# ETH_1G_MAGNET_HX5084.net
KiCad netlist of a schematic drawn in Altium Designer
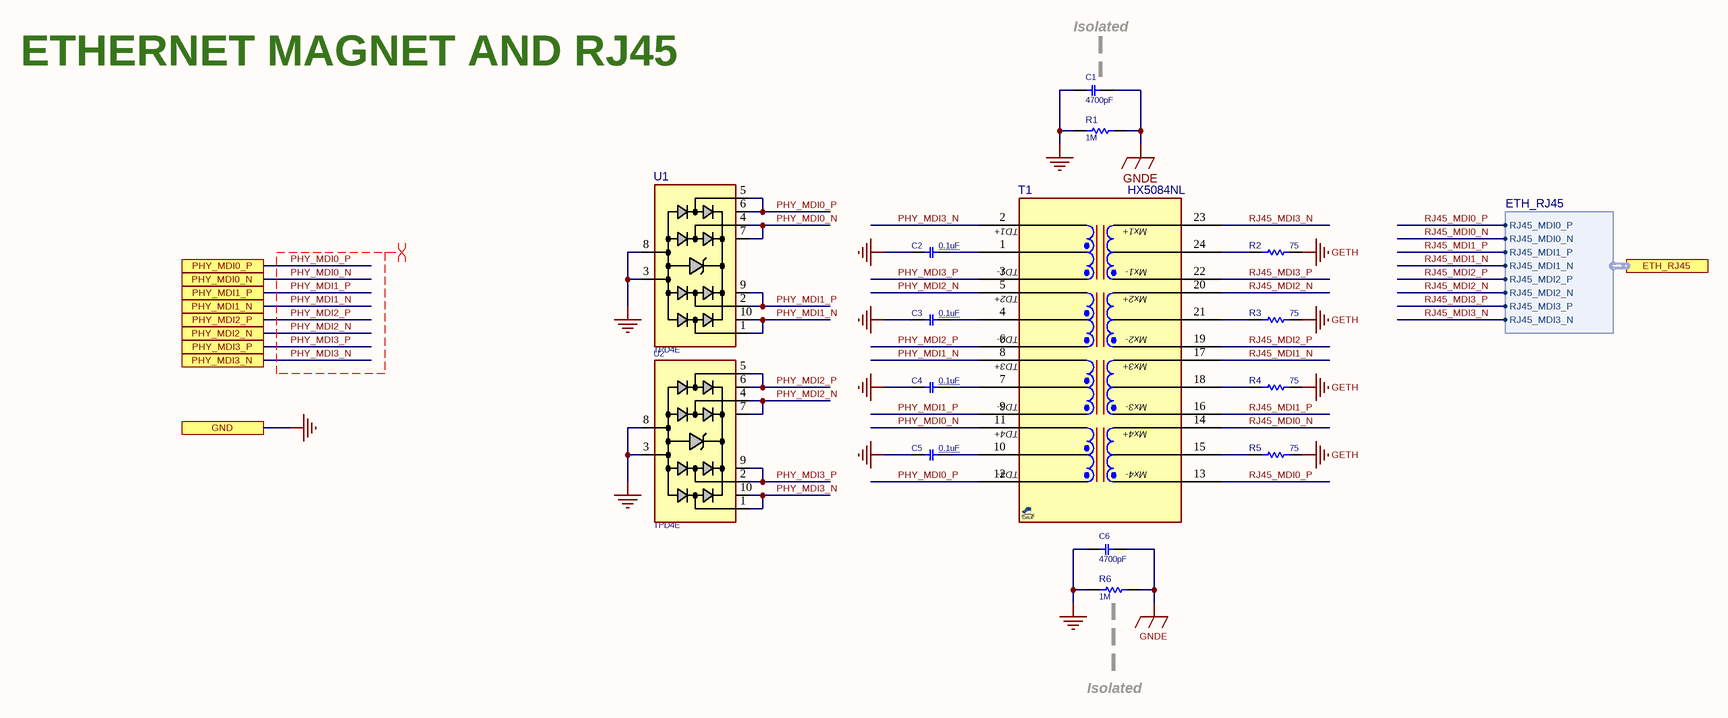
[diagram p0: ETH_1G_MAGNET_HX5084.SchDoc]

(export (version "E")
  (design (tool "Eeschema 10.0.6"))
  (components
    (comp (ref "C1")
      (value "4700pF")
      (footprint "C1206")
      (description "CAP, MLCC")
      (fields (field (name "MANF_P#") "NV1206B472K202CEGN") (field (name "MANF") "KEMET"))
      (libsource (lib "mlcc_smd_passive") (part "CAP_SMD_MLCC_68n1kv"))
    )
    (comp (ref "C2")
      (value "0.1uF")
      (footprint "C0402")
      (description "CAP, MLCC")
      (fields (field (name "MANF_P#") "MANF_PART#"))
      (libsource (lib "passive_smd") (part "CAP_SMD_MLCC_0402"))
    )
    (comp (ref "C3")
      (value "0.1uF")
      (footprint "C0402")
      (description "CAP, MLCC")
      (fields (field (name "MANF_P#") "MANF_PART#"))
      (libsource (lib "passive_smd") (part "CAP_SMD_MLCC_0402"))
    )
    (comp (ref "C4")
      (value "0.1uF")
      (footprint "C0402")
      (description "CAP, MLCC")
      (fields (field (name "MANF_P#") "MANF_PART#"))
      (libsource (lib "passive_smd") (part "CAP_SMD_MLCC_0402"))
    )
    (comp (ref "C5")
      (value "0.1uF")
      (footprint "C0402")
      (description "CAP, MLCC")
      (fields (field (name "MANF_P#") "MANF_PART#"))
      (libsource (lib "passive_smd") (part "CAP_SMD_MLCC_0402"))
    )
    (comp (ref "C6")
      (value "4700pF")
      (footprint "C1206")
      (description "CAP, MLCC")
      (fields (field (name "MANF_P#") "NV1206B472K202CEGN") (field (name "MANF") "KEMET"))
      (libsource (lib "mlcc_smd_passive") (part "CAP_SMD_MLCC_68n1kv"))
    )
    (comp (ref "R1")
      (value "1M")
      (footprint "R2512")
      (description "RESISTOR, SMD")
      (fields (field (name "MANF_P#") "FRC2512J105 TS"))
      (libsource (lib "chila_passive") (part "RES_SMD"))
    )
    (comp (ref "R2")
      (value "75")
      (footprint "R0402")
      (description "RESISTOR, SMD")
      (libsource (lib "passive_res_smd") (part "RES_SMD"))
    )
    (comp (ref "R3")
      (value "75")
      (footprint "R0402")
      (description "RESISTOR, SMD")
      (libsource (lib "passive_res_smd") (part "RES_SMD"))
    )
    (comp (ref "R4")
      (value "75")
      (footprint "R0402")
      (description "RESISTOR, SMD")
      (libsource (lib "passive_res_smd") (part "RES_SMD"))
    )
    (comp (ref "R5")
      (value "75")
      (footprint "R0402")
      (description "RESISTOR, SMD")
      (libsource (lib "passive_res_smd") (part "RES_SMD"))
    )
    (comp (ref "R6")
      (value "1M")
      (footprint "R2512")
      (description "RESISTOR, SMD")
      (fields (field (name "MANF_P#") "FRC2512J105 TS"))
      (libsource (lib "chila_passive") (part "RES_SMD"))
    )
    (comp (ref "T1")
      (value "HX5084NL")
      (footprint "SOG100_24")
      (description "Transformer, LAN 10/100/1000 Base-T, 1CT:1CT, 350uH")
      (fields (field (name "MANF") "Pulse"))
      (libsource (lib "transformer_ethernet") (part "HX5084NL_SO24"))
    )
    (comp (ref "U1")
      (value "TPD4E")
      (footprint "SON50_10_2510")
      (description "TVS, ESD PROTECT, 4CH,")
      (fields (field (name "MANF_P#") "TPD4E05U06DQA") (field (name "MANF") "Texas Instruments"))
      (libsource (lib "protect_tvs_esd_fuse") (part "TVS_X4_TPD4E05U06"))
    )
    (comp (ref "U2")
      (value "TPD4E")
      (footprint "SON50_10_2510")
      (description "TVS, ESD PROTECT, 4CH,")
      (fields (field (name "MANF_P#") "TPD4E05U06DQA") (field (name "MANF") "Texas Instruments"))
      (libsource (lib "protect_tvs_esd_fuse") (part "TVS_X4_TPD4E05U06"))
    )
  )
  (nets
    (net (code "2") (name "/PHY_MDI0_N") (class "Default")
      (node (ref "T1") (pin "11") (pinfunction "TD4+_11") (pintype "passive"))
      (node (ref "U1") (pin "4") (pinfunction "4_4") (pintype "passive"))
      (node (ref "U1") (pin "7") (pinfunction "7_7") (pintype "passive"))
    )
    (net (code "3") (name "/PHY_MDI0_P") (class "Default")
      (node (ref "T1") (pin "12") (pinfunction "TD4-_12") (pintype "passive"))
      (node (ref "U1") (pin "5") (pinfunction "5_5") (pintype "passive"))
      (node (ref "U1") (pin "6") (pinfunction "6_6") (pintype "passive"))
    )
    (net (code "4") (name "/PHY_MDI1_N") (class "Default")
      (node (ref "T1") (pin "8") (pinfunction "TD3+_8") (pintype "passive"))
      (node (ref "U1") (pin "1") (pinfunction "1_1") (pintype "passive"))
      (node (ref "U1") (pin "10") (pinfunction "10_10") (pintype "passive"))
    )
    (net (code "5") (name "/PHY_MDI1_P") (class "Default")
      (node (ref "T1") (pin "9") (pinfunction "TD3-_9") (pintype "passive"))
      (node (ref "U1") (pin "2") (pinfunction "2_2") (pintype "passive"))
      (node (ref "U1") (pin "9") (pinfunction "9_9") (pintype "passive"))
    )
    (net (code "6") (name "/PHY_MDI2_N") (class "Default")
      (node (ref "T1") (pin "5") (pinfunction "TD2+_5") (pintype "passive"))
      (node (ref "U2") (pin "4") (pinfunction "4_4") (pintype "passive"))
      (node (ref "U2") (pin "7") (pinfunction "7_7") (pintype "passive"))
    )
    (net (code "7") (name "/PHY_MDI2_P") (class "Default")
      (node (ref "T1") (pin "6") (pinfunction "TD2-_6") (pintype "passive"))
      (node (ref "U2") (pin "5") (pinfunction "5_5") (pintype "passive"))
      (node (ref "U2") (pin "6") (pinfunction "6_6") (pintype "passive"))
    )
    (net (code "8") (name "/PHY_MDI3_N") (class "Default")
      (node (ref "T1") (pin "2") (pinfunction "TD1+_2") (pintype "passive"))
      (node (ref "U2") (pin "1") (pinfunction "1_1") (pintype "passive"))
      (node (ref "U2") (pin "10") (pinfunction "10_10") (pintype "passive"))
    )
    (net (code "9") (name "/PHY_MDI3_P") (class "Default")
      (node (ref "T1") (pin "3") (pinfunction "TD1-_3") (pintype "passive"))
      (node (ref "U2") (pin "2") (pinfunction "2_2") (pintype "passive"))
      (node (ref "U2") (pin "9") (pinfunction "9_9") (pintype "passive"))
    )
    (net (code "10") (name "/RJ45_MDI0_N") (class "Default")
      (node (ref "T1") (pin "14") (pinfunction "MX4+_14") (pintype "passive"))
    )
    (net (code "11") (name "/RJ45_MDI0_P") (class "Default")
      (node (ref "T1") (pin "13") (pinfunction "MX4-_13") (pintype "passive"))
    )
    (net (code "12") (name "/RJ45_MDI1_N") (class "Default")
      (node (ref "T1") (pin "17") (pinfunction "MX3+_17") (pintype "passive"))
    )
    (net (code "13") (name "/RJ45_MDI1_P") (class "Default")
      (node (ref "T1") (pin "16") (pinfunction "MX3-_16") (pintype "passive"))
    )
    (net (code "14") (name "/RJ45_MDI2_N") (class "Default")
      (node (ref "T1") (pin "20") (pinfunction "MX2+_20") (pintype "passive"))
    )
    (net (code "15") (name "/RJ45_MDI2_P") (class "Default")
      (node (ref "T1") (pin "19") (pinfunction "MX2-_19") (pintype "passive"))
    )
    (net (code "16") (name "/RJ45_MDI3_N") (class "Default")
      (node (ref "T1") (pin "23") (pinfunction "MX1+_23") (pintype "passive"))
    )
    (net (code "17") (name "/RJ45_MDI3_P") (class "Default")
      (node (ref "T1") (pin "22") (pinfunction "MX1-_22") (pintype "passive"))
    )
    (net (code "19") (name "GETH") (class "Default")
      (node (ref "R2") (pin "1") (pinfunction "1_1") (pintype "passive"))
      (node (ref "R3") (pin "1") (pinfunction "1_1") (pintype "passive"))
      (node (ref "R4") (pin "1") (pinfunction "1_1") (pintype "passive"))
      (node (ref "R5") (pin "1") (pinfunction "1_1") (pintype "passive"))
    )
    (net (code "20") (name "GND") (class "Default")
      (node (ref "C1") (pin "1") (pinfunction "1_1") (pintype "passive"))
      (node (ref "C2") (pin "2") (pinfunction "2_2") (pintype "passive"))
      (node (ref "C3") (pin "2") (pinfunction "2_2") (pintype "passive"))
      (node (ref "C4") (pin "2") (pinfunction "2_2") (pintype "passive"))
      (node (ref "C5") (pin "2") (pinfunction "2_2") (pintype "passive"))
      (node (ref "C6") (pin "1") (pinfunction "1_1") (pintype "passive"))
      (node (ref "R1") (pin "2") (pinfunction "2_2") (pintype "passive"))
      (node (ref "R6") (pin "2") (pinfunction "2_2") (pintype "passive"))
      (node (ref "U1") (pin "3") (pinfunction "3_3") (pintype "passive"))
      (node (ref "U1") (pin "8") (pinfunction "8_8") (pintype "passive"))
      (node (ref "U2") (pin "3") (pinfunction "3_3") (pintype "passive"))
      (node (ref "U2") (pin "8") (pinfunction "8_8") (pintype "passive"))
    )
    (net (code "21") (name "GNDE") (class "Default")
      (node (ref "C1") (pin "2") (pinfunction "2_2") (pintype "passive"))
      (node (ref "C6") (pin "2") (pinfunction "2_2") (pintype "passive"))
      (node (ref "R1") (pin "1") (pinfunction "1_1") (pintype "passive"))
      (node (ref "R6") (pin "1") (pinfunction "1_1") (pintype "passive"))
    )
    (net (code "22") (name "Net-(T1-MCT1)") (class "Default")
      (node (ref "R2") (pin "2") (pinfunction "2_2") (pintype "passive"))
      (node (ref "T1") (pin "24") (pinfunction "MCT1_24") (pintype "passive"))
    )
    (net (code "23") (name "Net-(T1-MCT2)") (class "Default")
      (node (ref "R3") (pin "2") (pinfunction "2_2") (pintype "passive"))
      (node (ref "T1") (pin "21") (pinfunction "MCT2_21") (pintype "passive"))
    )
    (net (code "24") (name "Net-(T1-MCT3)") (class "Default")
      (node (ref "R4") (pin "2") (pinfunction "2_2") (pintype "passive"))
      (node (ref "T1") (pin "18") (pinfunction "MCT3_18") (pintype "passive"))
    )
    (net (code "25") (name "Net-(T1-MCT4)") (class "Default")
      (node (ref "R5") (pin "2") (pinfunction "2_2") (pintype "passive"))
      (node (ref "T1") (pin "15") (pinfunction "MCT4_15") (pintype "passive"))
    )
    (net (code "26") (name "Net-(T1-TCT1)") (class "Default")
      (node (ref "C2") (pin "1") (pinfunction "1_1") (pintype "passive"))
      (node (ref "T1") (pin "1") (pinfunction "TCT1_1") (pintype "passive"))
    )
    (net (code "27") (name "Net-(T1-TCT2)") (class "Default")
      (node (ref "C3") (pin "1") (pinfunction "1_1") (pintype "passive"))
      (node (ref "T1") (pin "4") (pinfunction "TCT2_4") (pintype "passive"))
    )
    (net (code "28") (name "Net-(T1-TCT3)") (class "Default")
      (node (ref "C4") (pin "1") (pinfunction "1_1") (pintype "passive"))
      (node (ref "T1") (pin "7") (pinfunction "TCT3_7") (pintype "passive"))
    )
    (net (code "29") (name "Net-(T1-TCT4)") (class "Default")
      (node (ref "C5") (pin "1") (pinfunction "1_1") (pintype "passive"))
      (node (ref "T1") (pin "10") (pinfunction "TCT4_10") (pintype "passive"))
    )
  )
)
